# Voltage_Regulators.net
KiCad netlist of a schematic drawn in Altium Designer
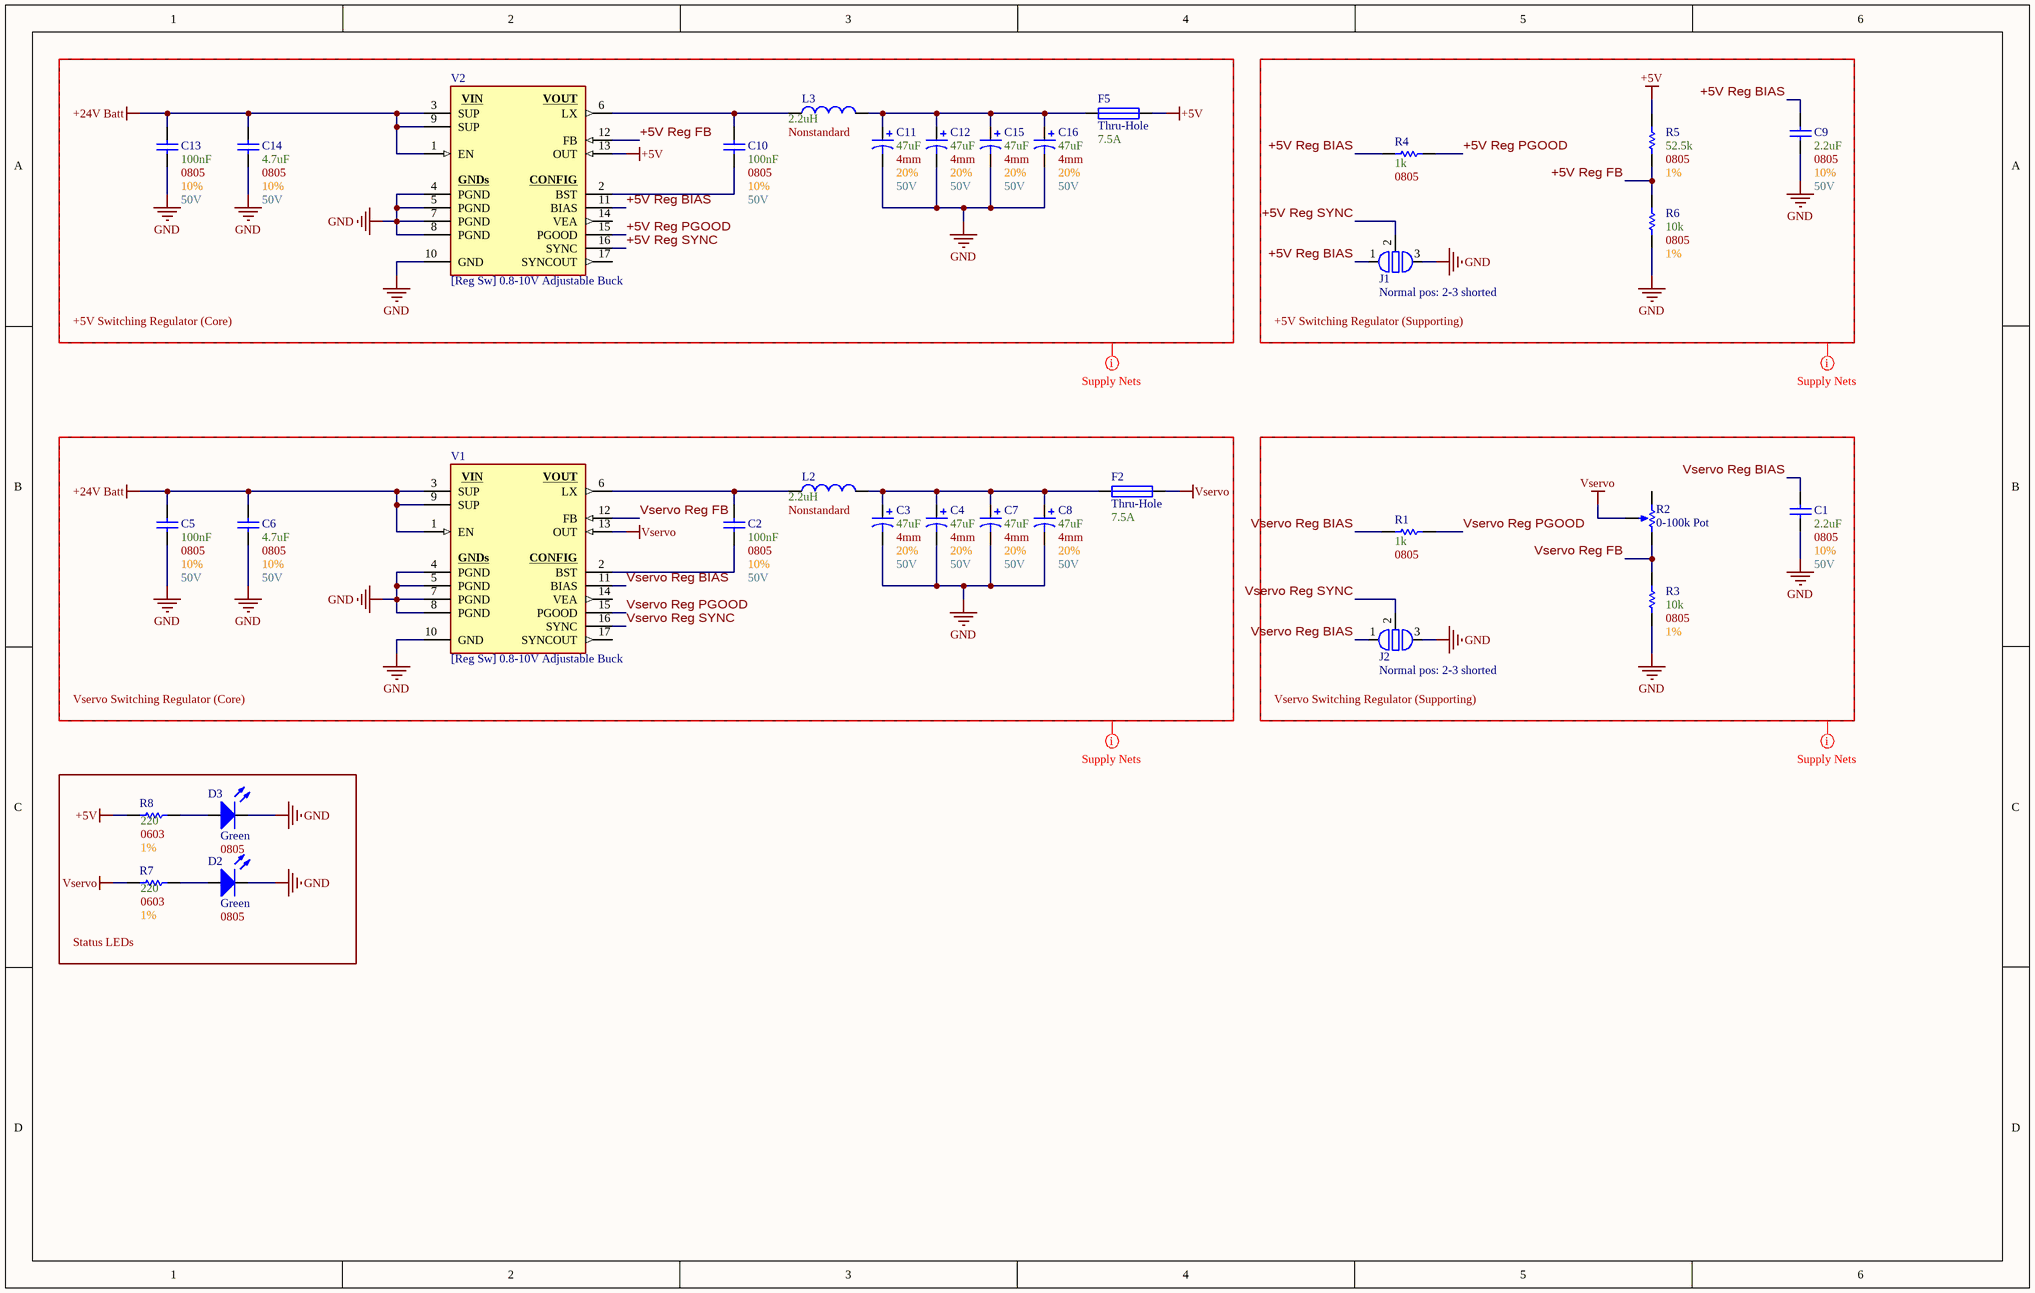
[diagram p0: Voltage Regulators.SchDoc]

(export (version "E")
  (design (tool "Eeschema 10.0.6"))
  (components
    (comp (ref "C1")
      (value "SMD Nonpolarized")
      (footprint "[Cap] SMD 0805")
      (fields
        (field (name "VOLTAGE") "50V")
        (field (name "TOLERANCE") "10%")
        (field (name "SIZE PACKAGE") "0805")
        (field (name "CAPACITANCE") "2.2uF")
      )
      (libsource (lib "RADM Components") (part "[Cap] SMD Nonpolarized"))
    )
    (comp (ref "C2")
      (value "SMD Nonpolarized")
      (footprint "[Cap] SMD 0805")
      (fields
        (field (name "VOLTAGE") "50V")
        (field (name "TOLERANCE") "10%")
        (field (name "SIZE PACKAGE") "0805")
        (field (name "CAPACITANCE") "100nF")
      )
      (libsource (lib "RADM Components") (part "[Cap] SMD Nonpolarized"))
    )
    (comp (ref "C3")
      (value "SMD Polarized")
      (footprint "[Cap] SMD Polarized, 4mm")
      (fields
        (field (name "TOLERANCE") "20%")
        (field (name "MAX VOLTAGE") "50V")
        (field (name "CAPACITANCE") "47uF")
        (field (name "DIAMETER") "4mm")
      )
      (libsource (lib "RADM Components") (part "[Cap] SMD Polarized"))
    )
    (comp (ref "C4")
      (value "SMD Polarized")
      (footprint "[Cap] SMD Polarized, 4mm")
      (fields
        (field (name "TOLERANCE") "20%")
        (field (name "MAX VOLTAGE") "50V")
        (field (name "CAPACITANCE") "47uF")
        (field (name "DIAMETER") "4mm")
      )
      (libsource (lib "RADM Components") (part "[Cap] SMD Polarized"))
    )
    (comp (ref "C5")
      (value "SMD Nonpolarized")
      (footprint "[Cap] SMD 0805")
      (fields
        (field (name "VOLTAGE") "50V")
        (field (name "TOLERANCE") "10%")
        (field (name "SIZE PACKAGE") "0805")
        (field (name "CAPACITANCE") "100nF")
      )
      (libsource (lib "RADM Components") (part "[Cap] SMD Nonpolarized"))
    )
    (comp (ref "C6")
      (value "SMD Nonpolarized")
      (footprint "[Cap] SMD 0805")
      (fields
        (field (name "VOLTAGE") "50V")
        (field (name "TOLERANCE") "10%")
        (field (name "SIZE PACKAGE") "0805")
        (field (name "CAPACITANCE") "4.7uF")
      )
      (libsource (lib "RADM Components") (part "[Cap] SMD Nonpolarized"))
    )
    (comp (ref "C7")
      (value "SMD Polarized")
      (footprint "[Cap] SMD Polarized, 4mm")
      (fields
        (field (name "TOLERANCE") "20%")
        (field (name "MAX VOLTAGE") "50V")
        (field (name "CAPACITANCE") "47uF")
        (field (name "DIAMETER") "4mm")
      )
      (libsource (lib "RADM Components") (part "[Cap] SMD Polarized"))
    )
    (comp (ref "C8")
      (value "SMD Polarized")
      (footprint "[Cap] SMD Polarized, 4mm")
      (fields
        (field (name "TOLERANCE") "20%")
        (field (name "MAX VOLTAGE") "50V")
        (field (name "CAPACITANCE") "47uF")
        (field (name "DIAMETER") "4mm")
      )
      (libsource (lib "RADM Components") (part "[Cap] SMD Polarized"))
    )
    (comp (ref "C9")
      (value "SMD Nonpolarized")
      (footprint "[Cap] SMD 0805")
      (fields
        (field (name "VOLTAGE") "50V")
        (field (name "TOLERANCE") "10%")
        (field (name "SIZE PACKAGE") "0805")
        (field (name "CAPACITANCE") "2.2uF")
      )
      (libsource (lib "RADM Components") (part "[Cap] SMD Nonpolarized"))
    )
    (comp (ref "C10")
      (value "SMD Nonpolarized")
      (footprint "[Cap] SMD 0805")
      (fields
        (field (name "VOLTAGE") "50V")
        (field (name "TOLERANCE") "10%")
        (field (name "SIZE PACKAGE") "0805")
        (field (name "CAPACITANCE") "100nF")
      )
      (libsource (lib "RADM Components") (part "[Cap] SMD Nonpolarized"))
    )
    (comp (ref "C11")
      (value "SMD Polarized")
      (footprint "[Cap] SMD Polarized, 4mm")
      (fields
        (field (name "TOLERANCE") "20%")
        (field (name "MAX VOLTAGE") "50V")
        (field (name "CAPACITANCE") "47uF")
        (field (name "DIAMETER") "4mm")
      )
      (libsource (lib "RADM Components") (part "[Cap] SMD Polarized"))
    )
    (comp (ref "C12")
      (value "SMD Polarized")
      (footprint "[Cap] SMD Polarized, 4mm")
      (fields
        (field (name "TOLERANCE") "20%")
        (field (name "MAX VOLTAGE") "50V")
        (field (name "CAPACITANCE") "47uF")
        (field (name "DIAMETER") "4mm")
      )
      (libsource (lib "RADM Components") (part "[Cap] SMD Polarized"))
    )
    (comp (ref "C13")
      (value "SMD Nonpolarized")
      (footprint "[Cap] SMD 0805")
      (fields
        (field (name "VOLTAGE") "50V")
        (field (name "TOLERANCE") "10%")
        (field (name "SIZE PACKAGE") "0805")
        (field (name "CAPACITANCE") "100nF")
      )
      (libsource (lib "RADM Components") (part "[Cap] SMD Nonpolarized"))
    )
    (comp (ref "C14")
      (value "SMD Nonpolarized")
      (footprint "[Cap] SMD 0805")
      (fields
        (field (name "VOLTAGE") "50V")
        (field (name "TOLERANCE") "10%")
        (field (name "SIZE PACKAGE") "0805")
        (field (name "CAPACITANCE") "4.7uF")
      )
      (libsource (lib "RADM Components") (part "[Cap] SMD Nonpolarized"))
    )
    (comp (ref "C15")
      (value "SMD Polarized")
      (footprint "[Cap] SMD Polarized, 4mm")
      (fields
        (field (name "TOLERANCE") "20%")
        (field (name "MAX VOLTAGE") "50V")
        (field (name "CAPACITANCE") "47uF")
        (field (name "DIAMETER") "4mm")
      )
      (libsource (lib "RADM Components") (part "[Cap] SMD Polarized"))
    )
    (comp (ref "C16")
      (value "SMD Polarized")
      (footprint "[Cap] SMD Polarized, 4mm")
      (fields
        (field (name "TOLERANCE") "20%")
        (field (name "MAX VOLTAGE") "50V")
        (field (name "CAPACITANCE") "47uF")
        (field (name "DIAMETER") "4mm")
      )
      (libsource (lib "RADM Components") (part "[Cap] SMD Polarized"))
    )
    (comp (ref "D2")
      (value "SMD LED")
      (footprint "[LED] SMD 0805")
      (description "Generic")
      (fields (field (name "COLOR") "Green") (field (name "SIZE PACKAGE") "0805"))
      (libsource (lib "RADM Components") (part "[LED] SMD"))
    )
    (comp (ref "D3")
      (value "SMD LED")
      (footprint "[LED] SMD 0805")
      (description "Generic")
      (fields (field (name "COLOR") "Green") (field (name "SIZE PACKAGE") "0805"))
      (libsource (lib "RADM Components") (part "[LED] SMD"))
    )
    (comp (ref "F2")
      (value "Thru-Hole")
      (footprint "[Fuse] Thru-Hole Blade")
      (fields (field (name "CAPACITY") "7.5A"))
      (libsource (lib "RADM Components") (part "[Fuse] Thru-Hole Blade"))
    )
    (comp (ref "F5")
      (value "Thru-Hole")
      (footprint "[Fuse] Thru-Hole Blade")
      (fields (field (name "CAPACITY") "7.5A"))
      (libsource (lib "RADM Components") (part "[Fuse] Thru-Hole Blade"))
    )
    (comp (ref "J1")
      (value "Normal pos: 2-3 shorted")
      (footprint "[Jumper] Thru-Hole 3pin")
      (description "Clip Jumper")
      (libsource (lib "RADM Components") (part "[Jump] Thru-Hole 3pin"))
    )
    (comp (ref "J2")
      (value "Normal pos: 2-3 shorted")
      (footprint "[Jumper] Thru-Hole 3pin")
      (description "Clip Jumper")
      (libsource (lib "RADM Components") (part "[Jump] Thru-Hole 3pin"))
    )
    (comp (ref "L2")
      (value "SMD Inductor")
      (footprint "[Inductor] 7.4 X 6.6 X 3 MM")
      (fields (field (name "SIZE PACKAGE") "Nonstandard") (field (name "INDUCTANCE") "2.2uH"))
      (libsource (lib "RADM Components") (part "[Inductor] SMD Inductor"))
    )
    (comp (ref "L3")
      (value "SMD Inductor")
      (footprint "[Inductor] 7.4 X 6.6 X 3 MM")
      (fields (field (name "SIZE PACKAGE") "Nonstandard") (field (name "INDUCTANCE") "2.2uH"))
      (libsource (lib "RADM Components") (part "[Inductor] SMD Inductor"))
    )
    (comp (ref "R1")
      (value "[Res] SMD Resistor")
      (footprint "[Res] SMD 0805")
      (description "Generic")
      (fields (field (name "RESISTANCE") "1k") (field (name "SIZE PACKAGE") "0805"))
      (libsource (lib "RADM Components") (part "[Res] SMD Resistor"))
    )
    (comp (ref "R2")
      (value "0-100k Pot")
      (footprint "[Res] Pot 100k 0.5W")
      (libsource (lib "RADM Components") (part "[Res] Pot 100k 0.5W"))
    )
    (comp (ref "R3")
      (value "[Res] SMD Resistor")
      (footprint "[Res] SMD 0805")
      (description "Generic")
      (fields
        (field (name "TOLERANCE") "1%")
        (field (name "RESISTANCE") "10k")
        (field (name "SIZE PACKAGE") "0805")
      )
      (libsource (lib "RADM Components") (part "[Res] SMD Resistor"))
    )
    (comp (ref "R4")
      (value "[Res] SMD Resistor")
      (footprint "[Res] SMD 0805")
      (description "Generic")
      (fields (field (name "RESISTANCE") "1k") (field (name "SIZE PACKAGE") "0805"))
      (libsource (lib "RADM Components") (part "[Res] SMD Resistor"))
    )
    (comp (ref "R5")
      (value "[Res] SMD Resistor")
      (footprint "[Res] SMD 0805")
      (description "Generic")
      (fields
        (field (name "TOLERANCE") "1%")
        (field (name "RESISTANCE") "52.5k")
        (field (name "SIZE PACKAGE") "0805")
      )
      (libsource (lib "RADM Components") (part "[Res] SMD Resistor"))
    )
    (comp (ref "R6")
      (value "[Res] SMD Resistor")
      (footprint "[Res] SMD 0805")
      (description "Generic")
      (fields
        (field (name "TOLERANCE") "1%")
        (field (name "RESISTANCE") "10k")
        (field (name "SIZE PACKAGE") "0805")
      )
      (libsource (lib "RADM Components") (part "[Res] SMD Resistor"))
    )
    (comp (ref "R7")
      (value "[Res] SMD Resistor")
      (footprint "[Res] SMD 0603")
      (description "Generic")
      (fields
        (field (name "RESISTANCE") "220")
        (field (name "SIZE PACKAGE") "0603")
        (field (name "TOLERANCE") "1%")
      )
      (libsource (lib "RADM Components") (part "[Res] SMD Resistor"))
    )
    (comp (ref "R8")
      (value "[Res] SMD Resistor")
      (footprint "[Res] SMD 0603")
      (description "Generic")
      (fields
        (field (name "RESISTANCE") "220")
        (field (name "SIZE PACKAGE") "0603")
        (field (name "TOLERANCE") "1%")
      )
      (libsource (lib "RADM Components") (part "[Res] SMD Resistor"))
    )
    (comp (ref "V1")
      (value "[Reg Sw] 0.8-10V Adjustable Buck")
      (footprint "[Reg] 0.8-10V Adjustable Buck")
      (description "MAX20408AFOF/VY+")
      (libsource (lib "RADM Components") (part "[Reg Sw] 0.8-10V Adjustable Buck"))
    )
    (comp (ref "V2")
      (value "[Reg Sw] 0.8-10V Adjustable Buck")
      (footprint "[Reg] 0.8-10V Adjustable Buck")
      (description "MAX20408AFOF/VY+")
      (libsource (lib "RADM Components") (part "[Reg Sw] 0.8-10V Adjustable Buck"))
    )
  )
  (nets
    (net (code "1") (name "+5V") (class "Default")
      (node (ref "F5") (pin "2") (pinfunction "2_2") (pintype "passive"))
      (node (ref "R5") (pin "2") (pinfunction "2_2") (pintype "passive"))
      (node (ref "R8") (pin "2") (pinfunction "2_2") (pintype "passive"))
      (node (ref "V2") (pin "13") (pinfunction "OUT_13") (pintype "input"))
    )
    (net (code "2") (name "+24V Batt") (class "Default")
      (node (ref "C13") (pin "2") (pinfunction "2_2") (pintype "passive"))
      (node (ref "C14") (pin "2") (pinfunction "2_2") (pintype "passive"))
      (node (ref "C5") (pin "2") (pinfunction "2_2") (pintype "passive"))
      (node (ref "C6") (pin "2") (pinfunction "2_2") (pintype "passive"))
      (node (ref "V1") (pin "1") (pinfunction "EN_1") (pintype "input"))
      (node (ref "V1") (pin "3") (pinfunction "SUP_3") (pintype "power_in"))
      (node (ref "V1") (pin "9") (pinfunction "SUP_9") (pintype "power_in"))
      (node (ref "V2") (pin "1") (pinfunction "EN_1") (pintype "input"))
      (node (ref "V2") (pin "3") (pinfunction "SUP_3") (pintype "power_in"))
      (node (ref "V2") (pin "9") (pinfunction "SUP_9") (pintype "power_in"))
    )
    (net (code "3") (name "/+5V Reg BIAS") (class "Default")
      (node (ref "C9") (pin "2") (pinfunction "2_2") (pintype "passive"))
      (node (ref "J1") (pin "1") (pintype "passive"))
      (node (ref "R4") (pin "1") (pinfunction "1_1") (pintype "passive"))
      (node (ref "V2") (pin "11") (pinfunction "BIAS_11") (pintype "power_in"))
    )
    (net (code "4") (name "/+5V Reg FB") (class "Default")
      (node (ref "R5") (pin "1") (pinfunction "1_1") (pintype "passive"))
      (node (ref "R6") (pin "2") (pinfunction "2_2") (pintype "passive"))
      (node (ref "V2") (pin "12") (pinfunction "FB_12") (pintype "input"))
    )
    (net (code "5") (name "/+5V Reg PGOOD") (class "Default")
      (node (ref "R4") (pin "2") (pinfunction "2_2") (pintype "passive"))
      (node (ref "V2") (pin "15") (pinfunction "PGOOD_15") (pintype "open_collector"))
    )
    (net (code "6") (name "/+5V Reg SYNC") (class "Default")
      (node (ref "J1") (pin "2") (pinfunction "Common_2") (pintype "power_in"))
      (node (ref "V2") (pin "16") (pinfunction "SYNC_16") (pintype "passive"))
    )
    (net (code "7") (name "/Vservo Reg BIAS") (class "Default")
      (node (ref "C1") (pin "2") (pinfunction "2_2") (pintype "passive"))
      (node (ref "J2") (pin "1") (pintype "passive"))
      (node (ref "R1") (pin "1") (pinfunction "1_1") (pintype "passive"))
      (node (ref "V1") (pin "11") (pinfunction "BIAS_11") (pintype "power_in"))
    )
    (net (code "8") (name "/Vservo Reg FB") (class "Default")
      (node (ref "R2") (pin "3") (pinfunction "BOT_3") (pintype "passive"))
      (node (ref "R3") (pin "2") (pinfunction "2_2") (pintype "passive"))
      (node (ref "V1") (pin "12") (pinfunction "FB_12") (pintype "input"))
    )
    (net (code "9") (name "/Vservo Reg PGOOD") (class "Default")
      (node (ref "R1") (pin "2") (pinfunction "2_2") (pintype "passive"))
      (node (ref "V1") (pin "15") (pinfunction "PGOOD_15") (pintype "open_collector"))
    )
    (net (code "10") (name "/Vservo Reg SYNC") (class "Default")
      (node (ref "J2") (pin "2") (pinfunction "Common_2") (pintype "power_in"))
      (node (ref "V1") (pin "16") (pinfunction "SYNC_16") (pintype "passive"))
    )
    (net (code "11") (name "GND") (class "Default")
      (node (ref "C1") (pin "1") (pinfunction "1_1") (pintype "passive"))
      (node (ref "C11") (pin "2") (pinfunction "2_2") (pintype "passive"))
      (node (ref "C12") (pin "2") (pinfunction "2_2") (pintype "passive"))
      (node (ref "C13") (pin "1") (pinfunction "1_1") (pintype "passive"))
      (node (ref "C14") (pin "1") (pinfunction "1_1") (pintype "passive"))
      (node (ref "C15") (pin "2") (pinfunction "2_2") (pintype "passive"))
      (node (ref "C16") (pin "2") (pinfunction "2_2") (pintype "passive"))
      (node (ref "C3") (pin "2") (pinfunction "2_2") (pintype "passive"))
      (node (ref "C4") (pin "2") (pinfunction "2_2") (pintype "passive"))
      (node (ref "C5") (pin "1") (pinfunction "1_1") (pintype "passive"))
      (node (ref "C6") (pin "1") (pinfunction "1_1") (pintype "passive"))
      (node (ref "C7") (pin "2") (pinfunction "2_2") (pintype "passive"))
      (node (ref "C8") (pin "2") (pinfunction "2_2") (pintype "passive"))
      (node (ref "C9") (pin "1") (pinfunction "1_1") (pintype "passive"))
      (node (ref "D2") (pin "2") (pinfunction "Cathode_2") (pintype "passive"))
      (node (ref "D3") (pin "2") (pinfunction "Cathode_2") (pintype "passive"))
      (node (ref "J1") (pin "3") (pintype "passive"))
      (node (ref "J2") (pin "3") (pintype "passive"))
      (node (ref "R3") (pin "1") (pinfunction "1_1") (pintype "passive"))
      (node (ref "R6") (pin "1") (pinfunction "1_1") (pintype "passive"))
      (node (ref "V1") (pin "10") (pinfunction "GND_10") (pintype "power_in"))
      (node (ref "V1") (pin "4") (pinfunction "PGND_4") (pintype "power_in"))
      (node (ref "V1") (pin "5") (pinfunction "PGND_5") (pintype "power_in"))
      (node (ref "V1") (pin "7") (pinfunction "PGND_7") (pintype "power_in"))
      (node (ref "V1") (pin "8") (pinfunction "PGND_8") (pintype "power_in"))
      (node (ref "V2") (pin "10") (pinfunction "GND_10") (pintype "power_in"))
      (node (ref "V2") (pin "4") (pinfunction "PGND_4") (pintype "power_in"))
      (node (ref "V2") (pin "5") (pinfunction "PGND_5") (pintype "power_in"))
      (node (ref "V2") (pin "7") (pinfunction "PGND_7") (pintype "power_in"))
      (node (ref "V2") (pin "8") (pinfunction "PGND_8") (pintype "power_in"))
    )
    (net (code "12") (name "Net-(C3-Pad1)") (class "Default")
      (node (ref "C3") (pin "1") (pinfunction "1_1") (pintype "passive"))
      (node (ref "C4") (pin "1") (pinfunction "1_1") (pintype "passive"))
      (node (ref "C7") (pin "1") (pinfunction "1_1") (pintype "passive"))
      (node (ref "C8") (pin "1") (pinfunction "1_1") (pintype "passive"))
      (node (ref "F2") (pin "1") (pinfunction "1_1") (pintype "passive"))
      (node (ref "L2") (pin "2") (pinfunction "2_2") (pintype "passive"))
    )
    (net (code "13") (name "Net-(C11-Pad1)") (class "Default")
      (node (ref "C11") (pin "1") (pinfunction "1_1") (pintype "passive"))
      (node (ref "C12") (pin "1") (pinfunction "1_1") (pintype "passive"))
      (node (ref "C15") (pin "1") (pinfunction "1_1") (pintype "passive"))
      (node (ref "C16") (pin "1") (pinfunction "1_1") (pintype "passive"))
      (node (ref "F5") (pin "1") (pinfunction "1_1") (pintype "passive"))
      (node (ref "L3") (pin "2") (pinfunction "2_2") (pintype "passive"))
    )
    (net (code "14") (name "Net-(D2-Anode)") (class "Default")
      (node (ref "D2") (pin "1") (pinfunction "Anode_1") (pintype "passive"))
      (node (ref "R7") (pin "1") (pinfunction "1_1") (pintype "passive"))
    )
    (net (code "15") (name "Net-(D3-Anode)") (class "Default")
      (node (ref "D3") (pin "1") (pinfunction "Anode_1") (pintype "passive"))
      (node (ref "R8") (pin "1") (pinfunction "1_1") (pintype "passive"))
    )
    (net (code "16") (name "Net-(V1-BST)") (class "Default")
      (node (ref "C2") (pin "1") (pinfunction "1_1") (pintype "passive"))
      (node (ref "V1") (pin "2") (pinfunction "BST_2") (pintype "power_in"))
    )
    (net (code "17") (name "Net-(V1-LX)") (class "Default")
      (node (ref "C2") (pin "2") (pinfunction "2_2") (pintype "passive"))
      (node (ref "L2") (pin "1") (pinfunction "1_1") (pintype "passive"))
      (node (ref "V1") (pin "6") (pinfunction "LX_6") (pintype "output"))
    )
    (net (code "18") (name "Net-(V2-BST)") (class "Default")
      (node (ref "C10") (pin "1") (pinfunction "1_1") (pintype "passive"))
      (node (ref "V2") (pin "2") (pinfunction "BST_2") (pintype "power_in"))
    )
    (net (code "19") (name "Net-(V2-LX)") (class "Default")
      (node (ref "C10") (pin "2") (pinfunction "2_2") (pintype "passive"))
      (node (ref "L3") (pin "1") (pinfunction "1_1") (pintype "passive"))
      (node (ref "V2") (pin "6") (pinfunction "LX_6") (pintype "output"))
    )
    (net (code "20") (name "Vservo") (class "Default")
      (node (ref "F2") (pin "2") (pinfunction "2_2") (pintype "passive"))
      (node (ref "R2") (pin "2") (pinfunction "TAP_2") (pintype "passive"))
      (node (ref "R7") (pin "2") (pinfunction "2_2") (pintype "passive"))
      (node (ref "V1") (pin "13") (pinfunction "OUT_13") (pintype "input"))
    )
    (net (code "21") (name "unconnected-(R2-TOP-Pad1)") (class "Default")
      (node (ref "R2") (pin "1") (pinfunction "TOP_1") (pintype "passive"))
    )
    (net (code "22") (name "unconnected-(V1-SYNCOUT-Pad17)") (class "Default")
      (node (ref "V1") (pin "17") (pinfunction "SYNCOUT_17") (pintype "output"))
    )
    (net (code "23") (name "unconnected-(V1-VEA-Pad14)") (class "Default")
      (node (ref "V1") (pin "14") (pinfunction "VEA_14") (pintype "output"))
    )
    (net (code "24") (name "unconnected-(V2-SYNCOUT-Pad17)") (class "Default")
      (node (ref "V2") (pin "17") (pinfunction "SYNCOUT_17") (pintype "output"))
    )
    (net (code "25") (name "unconnected-(V2-VEA-Pad14)") (class "Default")
      (node (ref "V2") (pin "14") (pinfunction "VEA_14") (pintype "output"))
    )
  )
)
